# Shield.net
KiCad netlist of a schematic drawn in Altium Designer
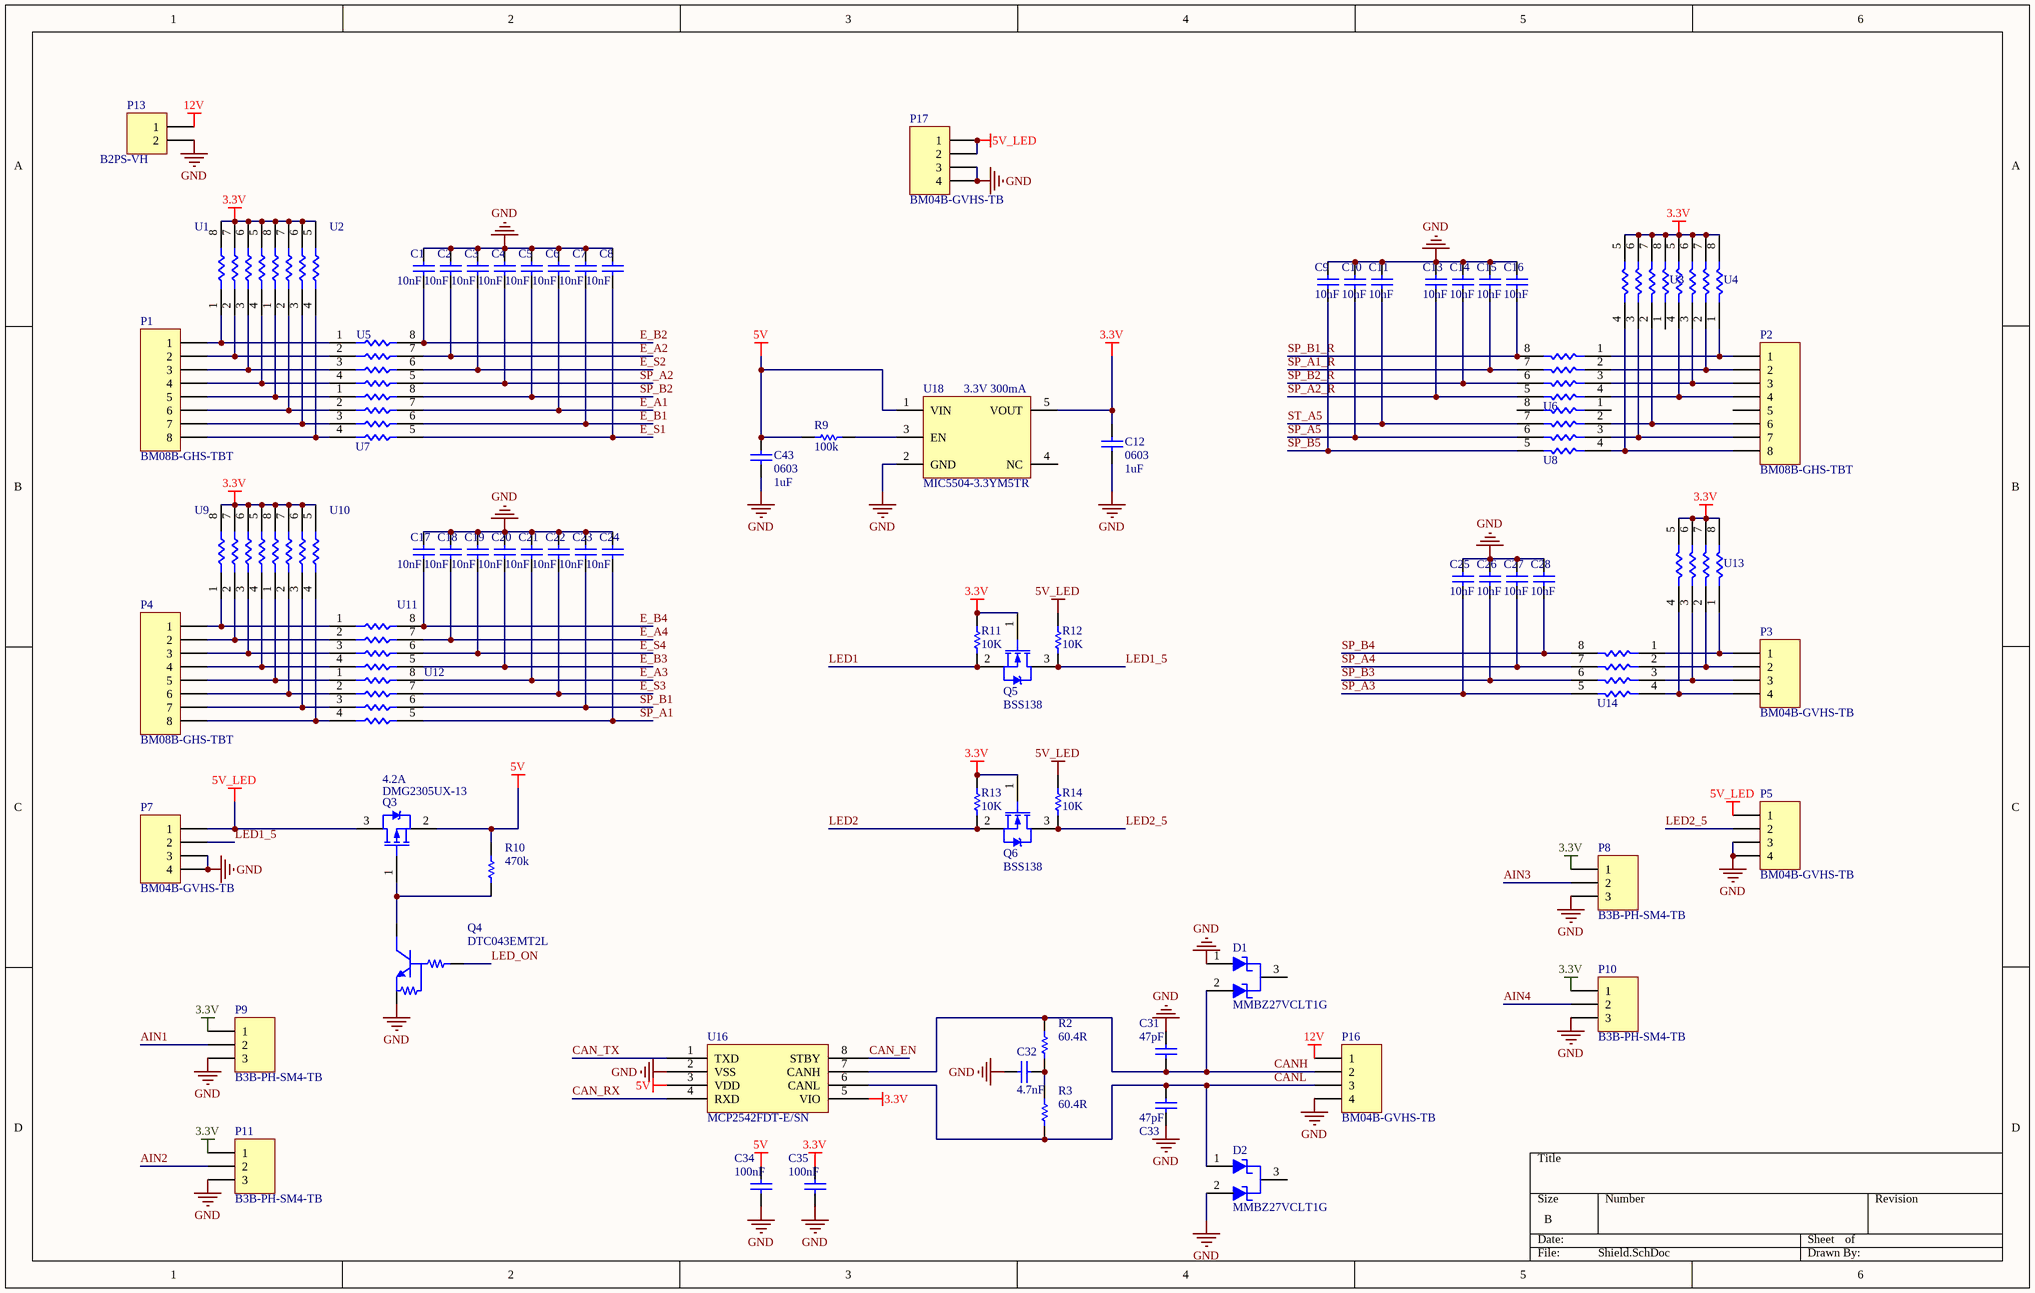
[diagram p0: Shield.SchDoc]

(export (version "E")
  (design (tool "Eeschema 10.0.6"))
  (components
    (comp (ref "C1")
      (value "10nF")
      (footprint "C0402")
      (description "Multilayer Ceramic Capacitor, 0.01 uF, 16 V, ± 5%, C0G (NP0), 0402 [1005 Metric]")
      (fields
        (field (name "MANUFACTURER") "Yageo")
        (field (name "MANUFACTURER PART NUMBER") "CC0402KRX7R7BB103")
      )
      (libsource (lib "Miscellaneous Devices") (part "Cap"))
    )
    (comp (ref "C2")
      (value "10nF")
      (footprint "C0402")
      (description "Multilayer Ceramic Capacitor, 0.01 uF, 16 V, ± 5%, C0G (NP0), 0402 [1005 Metric]")
      (fields
        (field (name "MANUFACTURER") "Yageo")
        (field (name "MANUFACTURER PART NUMBER") "CC0402KRX7R7BB103")
      )
      (libsource (lib "Miscellaneous Devices") (part "Cap"))
    )
    (comp (ref "C3")
      (value "10nF")
      (footprint "C0402")
      (description "Multilayer Ceramic Capacitor, 0.01 uF, 16 V, ± 5%, C0G (NP0), 0402 [1005 Metric]")
      (fields
        (field (name "MANUFACTURER") "Yageo")
        (field (name "MANUFACTURER PART NUMBER") "CC0402KRX7R7BB103")
      )
      (libsource (lib "Miscellaneous Devices") (part "Cap"))
    )
    (comp (ref "C4")
      (value "10nF")
      (footprint "C0402")
      (description "Multilayer Ceramic Capacitor, 0.01 uF, 16 V, ± 5%, C0G (NP0), 0402 [1005 Metric]")
      (fields
        (field (name "MANUFACTURER") "Yageo")
        (field (name "MANUFACTURER PART NUMBER") "CC0402KRX7R7BB103")
      )
      (libsource (lib "Miscellaneous Devices") (part "Cap"))
    )
    (comp (ref "C5")
      (value "10nF")
      (footprint "C0402")
      (description "Multilayer Ceramic Capacitor, 0.01 uF, 16 V, ± 5%, C0G (NP0), 0402 [1005 Metric]")
      (fields
        (field (name "MANUFACTURER") "Yageo")
        (field (name "MANUFACTURER PART NUMBER") "CC0402KRX7R7BB103")
      )
      (libsource (lib "Miscellaneous Devices") (part "Cap"))
    )
    (comp (ref "C6")
      (value "10nF")
      (footprint "C0402")
      (description "Multilayer Ceramic Capacitor, 0.01 uF, 16 V, ± 5%, C0G (NP0), 0402 [1005 Metric]")
      (fields
        (field (name "MANUFACTURER") "Yageo")
        (field (name "MANUFACTURER PART NUMBER") "CC0402KRX7R7BB103")
      )
      (libsource (lib "Miscellaneous Devices") (part "Cap"))
    )
    (comp (ref "C7")
      (value "10nF")
      (footprint "C0402")
      (description "Multilayer Ceramic Capacitor, 0.01 uF, 16 V, ± 5%, C0G (NP0), 0402 [1005 Metric]")
      (fields
        (field (name "MANUFACTURER") "Yageo")
        (field (name "MANUFACTURER PART NUMBER") "CC0402KRX7R7BB103")
      )
      (libsource (lib "Miscellaneous Devices") (part "Cap"))
    )
    (comp (ref "C8")
      (value "10nF")
      (footprint "C0402")
      (description "Multilayer Ceramic Capacitor, 0.01 uF, 16 V, ± 5%, C0G (NP0), 0402 [1005 Metric]")
      (fields
        (field (name "MANUFACTURER") "Yageo")
        (field (name "MANUFACTURER PART NUMBER") "CC0402KRX7R7BB103")
      )
      (libsource (lib "Miscellaneous Devices") (part "Cap"))
    )
    (comp (ref "C9")
      (value "10nF")
      (footprint "C0402")
      (description "Multilayer Ceramic Capacitor, 0.01 uF, 16 V, ± 5%, C0G (NP0), 0402 [1005 Metric]")
      (fields
        (field (name "MANUFACTURER") "Yageo")
        (field (name "MANUFACTURER PART NUMBER") "CC0402KRX7R7BB103")
      )
      (libsource (lib "Miscellaneous Devices") (part "Cap"))
    )
    (comp (ref "C10")
      (value "10nF")
      (footprint "C0402")
      (description "Multilayer Ceramic Capacitor, 0.01 uF, 16 V, ± 5%, C0G (NP0), 0402 [1005 Metric]")
      (fields
        (field (name "MANUFACTURER") "Yageo")
        (field (name "MANUFACTURER PART NUMBER") "CC0402KRX7R7BB103")
      )
      (libsource (lib "Miscellaneous Devices") (part "Cap"))
    )
    (comp (ref "C11")
      (value "10nF")
      (footprint "C0402")
      (description "Multilayer Ceramic Capacitor, 0.01 uF, 16 V, ± 5%, C0G (NP0), 0402 [1005 Metric]")
      (fields
        (field (name "MANUFACTURER") "Yageo")
        (field (name "MANUFACTURER PART NUMBER") "CC0402KRX7R7BB103")
      )
      (libsource (lib "Miscellaneous Devices") (part "Cap"))
    )
    (comp (ref "C12")
      (value "0603")
      (footprint "C0603")
      (description "Capacitor")
      (fields (field (name "ALTIUM_VALUE") "1uF") (field (name "PUBLISHER") "Altium Limited"))
      (libsource (lib "Miscellaneous Devices") (part "Cap"))
    )
    (comp (ref "C13")
      (value "10nF")
      (footprint "C0402")
      (description "Multilayer Ceramic Capacitor, 0.01 uF, 16 V, ± 5%, C0G (NP0), 0402 [1005 Metric]")
      (fields
        (field (name "MANUFACTURER") "Yageo")
        (field (name "MANUFACTURER PART NUMBER") "CC0402KRX7R7BB103")
      )
      (libsource (lib "Miscellaneous Devices") (part "Cap"))
    )
    (comp (ref "C14")
      (value "10nF")
      (footprint "C0402")
      (description "Multilayer Ceramic Capacitor, 0.01 uF, 16 V, ± 5%, C0G (NP0), 0402 [1005 Metric]")
      (fields
        (field (name "MANUFACTURER") "Yageo")
        (field (name "MANUFACTURER PART NUMBER") "CC0402KRX7R7BB103")
      )
      (libsource (lib "Miscellaneous Devices") (part "Cap"))
    )
    (comp (ref "C15")
      (value "10nF")
      (footprint "C0402")
      (description "Multilayer Ceramic Capacitor, 0.01 uF, 16 V, ± 5%, C0G (NP0), 0402 [1005 Metric]")
      (fields
        (field (name "MANUFACTURER") "Yageo")
        (field (name "MANUFACTURER PART NUMBER") "CC0402KRX7R7BB103")
      )
      (libsource (lib "Miscellaneous Devices") (part "Cap"))
    )
    (comp (ref "C16")
      (value "10nF")
      (footprint "C0402")
      (description "Multilayer Ceramic Capacitor, 0.01 uF, 16 V, ± 5%, C0G (NP0), 0402 [1005 Metric]")
      (fields
        (field (name "MANUFACTURER") "Yageo")
        (field (name "MANUFACTURER PART NUMBER") "CC0402KRX7R7BB103")
      )
      (libsource (lib "Miscellaneous Devices") (part "Cap"))
    )
    (comp (ref "C17")
      (value "10nF")
      (footprint "C0402")
      (description "Multilayer Ceramic Capacitor, 0.01 uF, 16 V, ± 5%, C0G (NP0), 0402 [1005 Metric]")
      (fields
        (field (name "MANUFACTURER") "Yageo")
        (field (name "MANUFACTURER PART NUMBER") "CC0402KRX7R7BB103")
      )
      (libsource (lib "Miscellaneous Devices") (part "Cap"))
    )
    (comp (ref "C18")
      (value "10nF")
      (footprint "C0402")
      (description "Multilayer Ceramic Capacitor, 0.01 uF, 16 V, ± 5%, C0G (NP0), 0402 [1005 Metric]")
      (fields
        (field (name "MANUFACTURER") "Yageo")
        (field (name "MANUFACTURER PART NUMBER") "CC0402KRX7R7BB103")
      )
      (libsource (lib "Miscellaneous Devices") (part "Cap"))
    )
    (comp (ref "C19")
      (value "10nF")
      (footprint "C0402")
      (description "Multilayer Ceramic Capacitor, 0.01 uF, 16 V, ± 5%, C0G (NP0), 0402 [1005 Metric]")
      (fields
        (field (name "MANUFACTURER") "Yageo")
        (field (name "MANUFACTURER PART NUMBER") "CC0402KRX7R7BB103")
      )
      (libsource (lib "Miscellaneous Devices") (part "Cap"))
    )
    (comp (ref "C20")
      (value "10nF")
      (footprint "C0402")
      (description "Multilayer Ceramic Capacitor, 0.01 uF, 16 V, ± 5%, C0G (NP0), 0402 [1005 Metric]")
      (fields
        (field (name "MANUFACTURER") "Yageo")
        (field (name "MANUFACTURER PART NUMBER") "CC0402KRX7R7BB103")
      )
      (libsource (lib "Miscellaneous Devices") (part "Cap"))
    )
    (comp (ref "C21")
      (value "10nF")
      (footprint "C0402")
      (description "Multilayer Ceramic Capacitor, 0.01 uF, 16 V, ± 5%, C0G (NP0), 0402 [1005 Metric]")
      (fields
        (field (name "MANUFACTURER") "Yageo")
        (field (name "MANUFACTURER PART NUMBER") "CC0402KRX7R7BB103")
      )
      (libsource (lib "Miscellaneous Devices") (part "Cap"))
    )
    (comp (ref "C22")
      (value "10nF")
      (footprint "C0402")
      (description "Multilayer Ceramic Capacitor, 0.01 uF, 16 V, ± 5%, C0G (NP0), 0402 [1005 Metric]")
      (fields
        (field (name "MANUFACTURER") "Yageo")
        (field (name "MANUFACTURER PART NUMBER") "CC0402KRX7R7BB103")
      )
      (libsource (lib "Miscellaneous Devices") (part "Cap"))
    )
    (comp (ref "C23")
      (value "10nF")
      (footprint "C0402")
      (description "Multilayer Ceramic Capacitor, 0.01 uF, 16 V, ± 5%, C0G (NP0), 0402 [1005 Metric]")
      (fields
        (field (name "MANUFACTURER") "Yageo")
        (field (name "MANUFACTURER PART NUMBER") "CC0402KRX7R7BB103")
      )
      (libsource (lib "Miscellaneous Devices") (part "Cap"))
    )
    (comp (ref "C24")
      (value "10nF")
      (footprint "C0402")
      (description "Multilayer Ceramic Capacitor, 0.01 uF, 16 V, ± 5%, C0G (NP0), 0402 [1005 Metric]")
      (fields
        (field (name "MANUFACTURER") "Yageo")
        (field (name "MANUFACTURER PART NUMBER") "CC0402KRX7R7BB103")
      )
      (libsource (lib "Miscellaneous Devices") (part "Cap"))
    )
    (comp (ref "C25")
      (value "10nF")
      (footprint "C0402")
      (description "Multilayer Ceramic Capacitor, 0.01 uF, 16 V, ± 5%, C0G (NP0), 0402 [1005 Metric]")
      (fields
        (field (name "MANUFACTURER") "Yageo")
        (field (name "MANUFACTURER PART NUMBER") "CC0402KRX7R7BB103")
      )
      (libsource (lib "Miscellaneous Devices") (part "Cap"))
    )
    (comp (ref "C26")
      (value "10nF")
      (footprint "C0402")
      (description "Multilayer Ceramic Capacitor, 0.01 uF, 16 V, ± 5%, C0G (NP0), 0402 [1005 Metric]")
      (fields
        (field (name "MANUFACTURER") "Yageo")
        (field (name "MANUFACTURER PART NUMBER") "CC0402KRX7R7BB103")
      )
      (libsource (lib "Miscellaneous Devices") (part "Cap"))
    )
    (comp (ref "C27")
      (value "10nF")
      (footprint "C0402")
      (description "Multilayer Ceramic Capacitor, 0.01 uF, 16 V, ± 5%, C0G (NP0), 0402 [1005 Metric]")
      (fields
        (field (name "MANUFACTURER") "Yageo")
        (field (name "MANUFACTURER PART NUMBER") "CC0402KRX7R7BB103")
      )
      (libsource (lib "Miscellaneous Devices") (part "Cap"))
    )
    (comp (ref "C28")
      (value "10nF")
      (footprint "C0402")
      (description "Multilayer Ceramic Capacitor, 0.01 uF, 16 V, ± 5%, C0G (NP0), 0402 [1005 Metric]")
      (fields
        (field (name "MANUFACTURER") "Yageo")
        (field (name "MANUFACTURER PART NUMBER") "CC0402KRX7R7BB103")
      )
      (libsource (lib "Miscellaneous Devices") (part "Cap"))
    )
    (comp (ref "C31")
      (value "47pF")
      (footprint "C0402")
      (description "Cap Cer 47PF 100V C0G/NP0 0402")
      (fields
        (field (name "MANUFACTURER") "Wurth Electronics")
        (field (name "MANUFACTURER PART NUMBER") "885012005078")
      )
      (libsource (lib "Miscellaneous Devices") (part "Cap"))
    )
    (comp (ref "C32")
      (value "4.7nF")
      (footprint "C0402")
      (description "Cap Cer 4700PF 100V X7R 0402")
      (fields
        (field (name "MANUFACTURER") "Wurth Electronics")
        (field (name "MANUFACTURER PART NUMBER") "885012205084")
      )
      (libsource (lib "Miscellaneous Devices") (part "Cap"))
    )
    (comp (ref "C33")
      (value "47pF")
      (footprint "C0402")
      (description "Cap Cer 47PF 100V C0G/NP0 0402")
      (fields
        (field (name "MANUFACTURER") "Wurth Electronics")
        (field (name "MANUFACTURER PART NUMBER") "885012005078")
      )
      (libsource (lib "Miscellaneous Devices") (part "Cap"))
    )
    (comp (ref "C34")
      (value "100nF")
      (footprint "C0402")
      (description "100nF ±10% 16V X7R 0402 Multilayer Ceramic Capacitors MLCC - SMD/SMT RoHS")
      (fields
        (field (name "MANUFACTURER") "KEMET")
        (field (name "MANUFACTURER PART NUMBER") "C0402C104K4RAC-TU")
      )
      (libsource (lib "Miscellaneous Devices") (part "Cap"))
    )
    (comp (ref "C35")
      (value "100nF")
      (footprint "C0402")
      (description "100nF ±10% 16V X7R 0402 Multilayer Ceramic Capacitors MLCC - SMD/SMT RoHS")
      (fields
        (field (name "MANUFACTURER") "KEMET")
        (field (name "MANUFACTURER PART NUMBER") "C0402C104K4RAC-TU")
      )
      (libsource (lib "Miscellaneous Devices") (part "Cap"))
    )
    (comp (ref "C43")
      (value "0603")
      (footprint "C0603")
      (description "Capacitor")
      (fields (field (name "ALTIUM_VALUE") "1uF") (field (name "PUBLISHER") "Altium Limited"))
      (libsource (lib "Miscellaneous Devices") (part "Cap"))
    )
    (comp (ref "D1")
      (value "MMBZ27VCLT1G")
      (footprint "SOT-23")
      (description "TVS DIODE 22VWM 38VC SOT23")
      (fields (field (name "MANUFACTURER") "ON Semiconductor"))
      (libsource (lib "Schlib1") (part "MMBZ27VCLT1G"))
    )
    (comp (ref "D2")
      (value "MMBZ27VCLT1G")
      (footprint "SOT-23")
      (description "TVS DIODE 22VWM 38VC SOT23")
      (fields (field (name "MANUFACTURER") "ON Semiconductor"))
      (libsource (lib "Schlib1") (part "MMBZ27VCLT1G"))
    )
    (comp (ref "P1")
      (value "BM08B-GHS-TBT")
      (footprint "CONN-BM08B-GHS-TBT")
      (description "Header, 8-Pin")
      (fields (field (name "MANUFACTURER") "JST"))
      (libsource (lib "Miscellaneous Connectors") (part "Header 8"))
    )
    (comp (ref "P2")
      (value "BM08B-GHS-TBT")
      (footprint "CONN-BM08B-GHS-TBT - INVERTED")
      (description "Header, 8-Pin")
      (fields (field (name "MANUFACTURER") "JST"))
      (libsource (lib "") (part "Header 8_1"))
    )
    (comp (ref "P3")
      (value "BM04B-GVHS-TB")
      (footprint "CONN-SM04B-GHSV-TB - INVERTED")
      (description "Conn Header SMD 4POS 1.25MM")
      (fields (field (name "MANUFACTURER") "JST"))
      (libsource (lib "") (part "Header 4_1"))
    )
    (comp (ref "P4")
      (value "BM08B-GHS-TBT")
      (footprint "CONN-BM08B-GHS-TBT")
      (description "Header, 8-Pin")
      (fields (field (name "MANUFACTURER") "JST"))
      (libsource (lib "Miscellaneous Connectors") (part "Header 8"))
    )
    (comp (ref "P5")
      (value "BM04B-GVHS-TB")
      (footprint "CONN-SM04B-GHSV-TB - INVERTED")
      (description "Conn Header SMD 4POS 1.25MM")
      (fields (field (name "MANUFACTURER") "JST"))
      (libsource (lib "") (part "Header 4_1"))
    )
    (comp (ref "P7")
      (value "BM04B-GVHS-TB")
      (footprint "CONN-SM04B-GHSV-TB")
      (description "Conn Header SMD 4POS 1.25MM")
      (fields (field (name "MANUFACTURER") "JST"))
      (libsource (lib "Miscellaneous Connectors") (part "Header 4"))
    )
    (comp (ref "P8")
      (value "B3B-PH-SM4-TB")
      (footprint "CONN-B3B-PH-SM4-TB")
      (description "Header B3B-PH-SM4-TB, 2.00mm, 3-contacts, top entry, SMT /1000/reel")
      (fields (field (name "MANUFACTURER") "JST"))
      (libsource (lib "Miscellaneous Connectors") (part "Header 3"))
    )
    (comp (ref "P9")
      (value "B3B-PH-SM4-TB")
      (footprint "CONN-B3B-PH-SM4-TB")
      (description "Header B3B-PH-SM4-TB, 2.00mm, 3-contacts, top entry, SMT /1000/reel")
      (fields (field (name "MANUFACTURER") "JST"))
      (libsource (lib "Miscellaneous Connectors") (part "Header 3"))
    )
    (comp (ref "P10")
      (value "B3B-PH-SM4-TB")
      (footprint "CONN-B3B-PH-SM4-TB")
      (description "Header B3B-PH-SM4-TB, 2.00mm, 3-contacts, top entry, SMT /1000/reel")
      (fields (field (name "MANUFACTURER") "JST"))
      (libsource (lib "Miscellaneous Connectors") (part "Header 3"))
    )
    (comp (ref "P11")
      (value "B3B-PH-SM4-TB")
      (footprint "CONN-B3B-PH-SM4-TB")
      (description "Header B3B-PH-SM4-TB, 2.00mm, 3-contacts, top entry, SMT /1000/reel")
      (fields (field (name "MANUFACTURER") "JST"))
      (libsource (lib "Miscellaneous Connectors") (part "Header 3"))
    )
    (comp (ref "P13")
      (value "B2PS-VH")
      (footprint "CONN-B2PS-VH")
      (description "Header B2PS-VH, 3.96mm, 2-contacts, side entry, THT/1000/box")
      (fields (field (name "MANUFACTURER") "JST"))
      (libsource (lib "Miscellaneous Connectors") (part "Header 2"))
    )
    (comp (ref "P16")
      (value "BM04B-GVHS-TB")
      (footprint "CONN-SM04B-GHSV-TB - INVERTED")
      (description "Conn Header SMD 4POS 1.25MM")
      (fields (field (name "MANUFACTURER") "JST"))
      (libsource (lib "") (part "Header 4_1"))
    )
    (comp (ref "P17")
      (value "BM04B-GVHS-TB")
      (footprint "CONN-SM04B-GHSV-TB - INVERTED")
      (description "Conn Header SMD 4POS 1.25MM")
      (fields (field (name "MANUFACTURER") "JST"))
      (libsource (lib "Miscellaneous Connectors") (part "Header 4"))
    )
    (comp (ref "Q3")
      (value "DMG2305UX-13")
      (footprint "SOT23-3")
      (description "MOSFET P-CH 20V 4.2A SOT23")
      (fields (field (name "MANUFACTURER") "Diodes") (field (name "CONTINUOUS DRAIN CURRENT (ID)") "4.2A"))
      (libsource (lib "Symbols") (part "ZXMP10A13FTA"))
    )
    (comp (ref "Q4")
      (value "DTC043EMT2L")
      (footprint "SOT-723")
      (description "TRANS PREBIAS NPN 50V VMT3")
      (fields (field (name "MANUFACTURER") "Rohm"))
      (libsource (lib "Schlib1") (part "DTC043EMT2L"))
    )
    (comp (ref "Q5")
      (value "BSS138")
      (footprint "SOT-23")
      (description "N-Channel Power MOSFET")
      (libsource (lib "Miscellaneous Devices") (part "NMOS-2"))
    )
    (comp (ref "Q6")
      (value "BSS138")
      (footprint "SOT-23")
      (description "N-Channel Power MOSFET")
      (libsource (lib "Miscellaneous Devices") (part "NMOS-2"))
    )
    (comp (ref "R2")
      (value "60.4R")
      (footprint "R0402")
      (description "Res Thick Film 0402 60.4 Ohm 1% 1/16W ±100ppm/°C Molded SMD SMD Paper T/R")
      (fields
        (field (name "MANUFACTURER") "Vishay")
        (field (name "MANUFACTURER PART NUMBER") "CRCW040260R4FKED")
      )
      (libsource (lib "Miscellaneous Devices") (part "Res1"))
    )
    (comp (ref "R3")
      (value "60.4R")
      (footprint "R0402")
      (description "Res Thick Film 0402 60.4 Ohm 1% 1/16W ±100ppm/°C Molded SMD SMD Paper T/R")
      (fields
        (field (name "MANUFACTURER") "Vishay")
        (field (name "MANUFACTURER PART NUMBER") "CRCW040260R4FKED")
      )
      (libsource (lib "Miscellaneous Devices") (part "Res1"))
    )
    (comp (ref "R9")
      (value "100k")
      (footprint "R0402")
      (description "Res Thick Film 0402 60.4 Ohm 1% 1/16W ±100ppm/°C Molded SMD SMD Paper T/R")
      (libsource (lib "Miscellaneous Devices") (part "Res1"))
    )
    (comp (ref "R10")
      (value "470k")
      (footprint "R0402")
      (description "Res Thick Film 0402 60.4 Ohm 1% 1/16W ±100ppm/°C Molded SMD SMD Paper T/R")
      (libsource (lib "Miscellaneous Devices") (part "Res1"))
    )
    (comp (ref "R11")
      (value "10K")
      (footprint "R0402")
      (description "RES SMD 10 KOHM 1% 1/16W 0402")
      (fields (field (name "Comment") "Res1"))
      (libsource (lib "Miscellaneous Devices") (part "Res1"))
    )
    (comp (ref "R12")
      (value "10K")
      (footprint "R0402")
      (description "RES SMD 10 KOHM 1% 1/16W 0402")
      (fields (field (name "Comment") "Res1"))
      (libsource (lib "Miscellaneous Devices") (part "Res1"))
    )
    (comp (ref "R13")
      (value "10K")
      (footprint "R0402")
      (description "RES SMD 10 KOHM 1% 1/16W 0402")
      (fields (field (name "Comment") "Res1"))
      (libsource (lib "Miscellaneous Devices") (part "Res1"))
    )
    (comp (ref "R14")
      (value "10K")
      (footprint "R0402")
      (description "RES SMD 10 KOHM 1% 1/16W 0402")
      (fields (field (name "Comment") "Res1"))
      (libsource (lib "Miscellaneous Devices") (part "Res1"))
    )
    (comp (ref "U1")
      (value "CAY16-1002F4LF")
      (footprint "RES_ARRAY_4")
      (description "Res Thick Film Array 10K Ohm 1% 0.25W(1/4W) ±200ppm/C ISOL 8-Pin 1206(4 X 0603) Convex SMD T/R")
      (fields (field (name "MANUFACTURER") "Bourns") (field (name "TOLERANCE") "1%"))
      (libsource (lib "Schlib1") (part "ResArray4"))
    )
    (comp (ref "U2")
      (value "CAY16-1002F4LF")
      (footprint "RES_ARRAY_4")
      (description "Res Thick Film Array 10K Ohm 1% 0.25W(1/4W) ±200ppm/C ISOL 8-Pin 1206(4 X 0603) Convex SMD T/R")
      (fields (field (name "MANUFACTURER") "Bourns") (field (name "TOLERANCE") "1%"))
      (libsource (lib "Schlib1") (part "ResArray4"))
    )
    (comp (ref "U3")
      (value "CAY16-1002F4LF")
      (footprint "RES_ARRAY_4 - INVERTED")
      (description "Res Thick Film Array 10K Ohm 1% 0.25W(1/4W) ±200ppm/C ISOL 8-Pin 1206(4 X 0603) Convex SMD T/R")
      (fields (field (name "MANUFACTURER") "Bourns") (field (name "TOLERANCE") "1%"))
      (libsource (lib "Schlib1") (part "ResArray4"))
    )
    (comp (ref "U4")
      (value "CAY16-1002F4LF")
      (footprint "RES_ARRAY_4 - INVERTED")
      (description "Res Thick Film Array 10K Ohm 1% 0.25W(1/4W) ±200ppm/C ISOL 8-Pin 1206(4 X 0603) Convex SMD T/R")
      (fields (field (name "MANUFACTURER") "Bourns") (field (name "TOLERANCE") "1%"))
      (libsource (lib "Schlib1") (part "ResArray4"))
    )
    (comp (ref "U5")
      (value "CAY16-1002F4LF")
      (footprint "RES_ARRAY_4 - INVERTED")
      (description "Res Thick Film Array 10K Ohm 1% 0.25W(1/4W) ±200ppm/C ISOL 8-Pin 1206(4 X 0603) Convex SMD T/R")
      (fields (field (name "MANUFACTURER") "Bourns") (field (name "TOLERANCE") "1%"))
      (libsource (lib "Schlib1") (part "ResArray4"))
    )
    (comp (ref "U6")
      (value "CAY16-1002F4LF")
      (footprint "RES_ARRAY_4")
      (description "Res Thick Film Array 10K Ohm 1% 0.25W(1/4W) ±200ppm/C ISOL 8-Pin 1206(4 X 0603) Convex SMD T/R")
      (fields (field (name "MANUFACTURER") "Bourns") (field (name "TOLERANCE") "1%"))
      (libsource (lib "Schlib1") (part "ResArray4"))
    )
    (comp (ref "U7")
      (value "CAY16-1002F4LF")
      (footprint "RES_ARRAY_4 - INVERTED")
      (description "Res Thick Film Array 10K Ohm 1% 0.25W(1/4W) ±200ppm/C ISOL 8-Pin 1206(4 X 0603) Convex SMD T/R")
      (fields (field (name "MANUFACTURER") "Bourns") (field (name "TOLERANCE") "1%"))
      (libsource (lib "Schlib1") (part "ResArray4"))
    )
    (comp (ref "U8")
      (value "CAY16-1002F4LF")
      (footprint "RES_ARRAY_4")
      (description "Res Thick Film Array 10K Ohm 1% 0.25W(1/4W) ±200ppm/C ISOL 8-Pin 1206(4 X 0603) Convex SMD T/R")
      (fields (field (name "MANUFACTURER") "Bourns") (field (name "TOLERANCE") "1%"))
      (libsource (lib "Schlib1") (part "ResArray4"))
    )
    (comp (ref "U9")
      (value "CAY16-1002F4LF")
      (footprint "RES_ARRAY_4")
      (description "Res Thick Film Array 10K Ohm 1% 0.25W(1/4W) ±200ppm/C ISOL 8-Pin 1206(4 X 0603) Convex SMD T/R")
      (fields (field (name "MANUFACTURER") "Bourns") (field (name "TOLERANCE") "1%"))
      (libsource (lib "Schlib1") (part "ResArray4"))
    )
    (comp (ref "U10")
      (value "CAY16-1002F4LF")
      (footprint "RES_ARRAY_4")
      (description "Res Thick Film Array 10K Ohm 1% 0.25W(1/4W) ±200ppm/C ISOL 8-Pin 1206(4 X 0603) Convex SMD T/R")
      (fields (field (name "MANUFACTURER") "Bourns") (field (name "TOLERANCE") "1%"))
      (libsource (lib "Schlib1") (part "ResArray4"))
    )
    (comp (ref "U11")
      (value "CAY16-1002F4LF")
      (footprint "RES_ARRAY_4 - INVERTED")
      (description "Res Thick Film Array 10K Ohm 1% 0.25W(1/4W) ±200ppm/C ISOL 8-Pin 1206(4 X 0603) Convex SMD T/R")
      (fields (field (name "MANUFACTURER") "Bourns") (field (name "TOLERANCE") "1%"))
      (libsource (lib "Schlib1") (part "ResArray4"))
    )
    (comp (ref "U12")
      (value "CAY16-1002F4LF")
      (footprint "RES_ARRAY_4 - INVERTED")
      (description "Res Thick Film Array 10K Ohm 1% 0.25W(1/4W) ±200ppm/C ISOL 8-Pin 1206(4 X 0603) Convex SMD T/R")
      (fields (field (name "MANUFACTURER") "Bourns") (field (name "TOLERANCE") "1%"))
      (libsource (lib "Schlib1") (part "ResArray4"))
    )
    (comp (ref "U13")
      (value "CAY16-1002F4LF")
      (footprint "RES_ARRAY_4")
      (description "Res Thick Film Array 10K Ohm 1% 0.25W(1/4W) ±200ppm/C ISOL 8-Pin 1206(4 X 0603) Convex SMD T/R")
      (fields (field (name "MANUFACTURER") "Bourns") (field (name "TOLERANCE") "1%"))
      (libsource (lib "Schlib1") (part "ResArray4"))
    )
    (comp (ref "U14")
      (value "CAY16-1002F4LF")
      (footprint "RES_ARRAY_4")
      (description "Res Thick Film Array 10K Ohm 1% 0.25W(1/4W) ±200ppm/C ISOL 8-Pin 1206(4 X 0603) Convex SMD T/R")
      (fields (field (name "MANUFACTURER") "Bourns") (field (name "TOLERANCE") "1%"))
      (libsource (lib "Schlib1") (part "ResArray4"))
    )
    (comp (ref "U16")
      (value "MCP2542FDT-E/SN")
      (footprint "SOIC-8(150MIL)")
      (description "Can Interface IC Can Fd Transceiver - 8SOIC T/r")
      (fields (field (name "MANUFACTURER") "Microchip"))
      (libsource (lib "Schlib1") (part "MCP2542FDT-E/SN"))
    )
    (comp (ref "U18")
      (value "MIC5504-3.3YM5TR")
      (footprint "SOT23-5")
      (description "IC REG LINEAR 3.3V 300MA SOT23-5")
      (fields (field (name "MANUFACTURER") "Microchip Micrel") (field (name "ALTIUM_VALUE") "3.3V 300mA"))
      (libsource (lib "Footprints") (part "MIC5504-3.3YM5TR"))
    )
  )
  (nets
    (net (code "1") (name "/AIN1") (class "Default")
      (node (ref "P9") (pin "2") (pinfunction "2_2") (pintype "passive"))
    )
    (net (code "2") (name "/AIN2") (class "Default")
      (node (ref "P11") (pin "2") (pinfunction "2_2") (pintype "passive"))
    )
    (net (code "3") (name "/AIN3") (class "Default")
      (node (ref "P8") (pin "2") (pinfunction "2_2") (pintype "passive"))
    )
    (net (code "4") (name "/AIN4") (class "Default")
      (node (ref "P10") (pin "2") (pinfunction "2_2") (pintype "passive"))
    )
    (net (code "5") (name "/CANH") (class "Default")
      (node (ref "C31") (pin "1") (pinfunction "1_1") (pintype "passive"))
      (node (ref "D1") (pin "2") (pinfunction "C_2") (pintype "passive"))
      (node (ref "P16") (pin "2") (pinfunction "2_2") (pintype "passive"))
      (node (ref "R2") (pin "2") (pinfunction "2_2") (pintype "passive"))
      (node (ref "U16") (pin "7") (pinfunction "CANH_7") (pintype "passive"))
    )
    (net (code "6") (name "/CANL") (class "Default")
      (node (ref "C33") (pin "2") (pinfunction "2_2") (pintype "passive"))
      (node (ref "D2") (pin "1") (pinfunction "1_1") (pintype "passive"))
      (node (ref "P16") (pin "3") (pinfunction "3_3") (pintype "passive"))
      (node (ref "R3") (pin "1") (pinfunction "1_1") (pintype "passive"))
      (node (ref "U16") (pin "6") (pinfunction "CANL_6") (pintype "passive"))
    )
    (net (code "7") (name "/CAN_EN") (class "Default")
      (node (ref "U16") (pin "8") (pinfunction "STBY_8") (pintype "passive"))
    )
    (net (code "8") (name "/CAN_RX") (class "Default")
      (node (ref "U16") (pin "4") (pinfunction "RXD_4") (pintype "passive"))
    )
    (net (code "9") (name "/CAN_TX") (class "Default")
      (node (ref "U16") (pin "1") (pinfunction "TXD_1") (pintype "passive"))
    )
    (net (code "10") (name "/E_A1") (class "Default")
      (node (ref "C6") (pin "1") (pinfunction "1_1") (pintype "passive"))
      (node (ref "U7") (pin "7") (pinfunction "7_7") (pintype "passive"))
    )
    (net (code "11") (name "/E_A2") (class "Default")
      (node (ref "C2") (pin "1") (pinfunction "1_1") (pintype "passive"))
      (node (ref "U5") (pin "7") (pinfunction "7_7") (pintype "passive"))
    )
    (net (code "12") (name "/E_A3") (class "Default")
      (node (ref "C21") (pin "1") (pinfunction "1_1") (pintype "passive"))
      (node (ref "U12") (pin "8") (pinfunction "8_8") (pintype "passive"))
    )
    (net (code "13") (name "/E_A4") (class "Default")
      (node (ref "C18") (pin "1") (pinfunction "1_1") (pintype "passive"))
      (node (ref "U11") (pin "7") (pinfunction "7_7") (pintype "passive"))
    )
    (net (code "14") (name "/E_B1") (class "Default")
      (node (ref "C7") (pin "1") (pinfunction "1_1") (pintype "passive"))
      (node (ref "U7") (pin "6") (pinfunction "6_6") (pintype "passive"))
    )
    (net (code "15") (name "/E_B2") (class "Default")
      (node (ref "C1") (pin "1") (pinfunction "1_1") (pintype "passive"))
      (node (ref "U5") (pin "8") (pinfunction "8_8") (pintype "passive"))
    )
    (net (code "16") (name "/E_B3") (class "Default")
      (node (ref "C20") (pin "1") (pinfunction "1_1") (pintype "passive"))
      (node (ref "U11") (pin "5") (pinfunction "5_5") (pintype "passive"))
    )
    (net (code "17") (name "/E_B4") (class "Default")
      (node (ref "C17") (pin "1") (pinfunction "1_1") (pintype "passive"))
      (node (ref "U11") (pin "8") (pinfunction "8_8") (pintype "passive"))
    )
    (net (code "18") (name "/E_S1") (class "Default")
      (node (ref "C8") (pin "1") (pinfunction "1_1") (pintype "passive"))
      (node (ref "U7") (pin "5") (pinfunction "5_5") (pintype "passive"))
    )
    (net (code "19") (name "/E_S2") (class "Default")
      (node (ref "C3") (pin "1") (pinfunction "1_1") (pintype "passive"))
      (node (ref "U5") (pin "6") (pinfunction "6_6") (pintype "passive"))
    )
    (net (code "20") (name "/E_S3") (class "Default")
      (node (ref "C22") (pin "1") (pinfunction "1_1") (pintype "passive"))
      (node (ref "U12") (pin "7") (pinfunction "7_7") (pintype "passive"))
    )
    (net (code "21") (name "/E_S4") (class "Default")
      (node (ref "C19") (pin "1") (pinfunction "1_1") (pintype "passive"))
      (node (ref "U11") (pin "6") (pinfunction "6_6") (pintype "passive"))
    )
    (net (code "22") (name "/LED1") (class "Default")
      (node (ref "Q5") (pin "2") (pinfunction "S_2") (pintype "passive"))
      (node (ref "R11") (pin "2") (pinfunction "2_2") (pintype "passive"))
    )
    (net (code "23") (name "/LED1_5") (class "Default")
      (node (ref "P7") (pin "2") (pinfunction "2_2") (pintype "passive"))
      (node (ref "Q5") (pin "3") (pinfunction "D_3") (pintype "passive"))
      (node (ref "R12") (pin "2") (pinfunction "2_2") (pintype "passive"))
    )
    (net (code "24") (name "/LED2") (class "Default")
      (node (ref "Q6") (pin "2") (pinfunction "S_2") (pintype "passive"))
      (node (ref "R13") (pin "2") (pinfunction "2_2") (pintype "passive"))
    )
    (net (code "25") (name "/LED2_5") (class "Default")
      (node (ref "P5") (pin "2") (pinfunction "2_2") (pintype "passive"))
      (node (ref "Q6") (pin "3") (pinfunction "D_3") (pintype "passive"))
      (node (ref "R14") (pin "2") (pinfunction "2_2") (pintype "passive"))
    )
    (net (code "26") (name "/LED_ON") (class "Default")
      (node (ref "Q4") (pin "1") (pinfunction "B_1") (pintype "passive"))
    )
    (net (code "27") (name "/SP_A1") (class "Default")
      (node (ref "C24") (pin "1") (pinfunction "1_1") (pintype "passive"))
      (node (ref "U12") (pin "5") (pinfunction "5_5") (pintype "passive"))
    )
    (net (code "28") (name "/SP_A1_R") (class "Default")
      (node (ref "C15") (pin "1") (pinfunction "1_1") (pintype "passive"))
      (node (ref "U6") (pin "7") (pinfunction "7_7") (pintype "passive"))
    )
    (net (code "29") (name "/SP_A2") (class "Default")
      (node (ref "C4") (pin "1") (pinfunction "1_1") (pintype "passive"))
      (node (ref "U5") (pin "5") (pinfunction "5_5") (pintype "passive"))
    )
    (net (code "30") (name "/SP_A2_R") (class "Default")
      (node (ref "C13") (pin "1") (pinfunction "1_1") (pintype "passive"))
      (node (ref "U6") (pin "5") (pinfunction "5_5") (pintype "passive"))
    )
    (net (code "31") (name "/SP_A3") (class "Default")
      (node (ref "C25") (pin "1") (pinfunction "1_1") (pintype "passive"))
      (node (ref "U14") (pin "5") (pinfunction "5_5") (pintype "passive"))
    )
    (net (code "32") (name "/SP_A4") (class "Default")
      (node (ref "C27") (pin "1") (pinfunction "1_1") (pintype "passive"))
      (node (ref "U14") (pin "7") (pinfunction "7_7") (pintype "passive"))
    )
    (net (code "33") (name "/SP_A5") (class "Default")
      (node (ref "C10") (pin "1") (pinfunction "1_1") (pintype "passive"))
      (node (ref "U8") (pin "6") (pinfunction "6_6") (pintype "passive"))
    )
    (net (code "34") (name "/SP_B1") (class "Default")
      (node (ref "C23") (pin "1") (pinfunction "1_1") (pintype "passive"))
      (node (ref "U12") (pin "6") (pinfunction "6_6") (pintype "passive"))
    )
    (net (code "35") (name "/SP_B1_R") (class "Default")
      (node (ref "C16") (pin "1") (pinfunction "1_1") (pintype "passive"))
      (node (ref "U6") (pin "8") (pinfunction "8_8") (pintype "passive"))
    )
    (net (code "36") (name "/SP_B2") (class "Default")
      (node (ref "C5") (pin "1") (pinfunction "1_1") (pintype "passive"))
      (node (ref "U7") (pin "8") (pinfunction "8_8") (pintype "passive"))
    )
    (net (code "37") (name "/SP_B2_R") (class "Default")
      (node (ref "C14") (pin "1") (pinfunction "1_1") (pintype "passive"))
      (node (ref "U6") (pin "6") (pinfunction "6_6") (pintype "passive"))
    )
    (net (code "38") (name "/SP_B3") (class "Default")
      (node (ref "C26") (pin "1") (pinfunction "1_1") (pintype "passive"))
      (node (ref "U14") (pin "6") (pinfunction "6_6") (pintype "passive"))
    )
    (net (code "39") (name "/SP_B4") (class "Default")
      (node (ref "C28") (pin "1") (pinfunction "1_1") (pintype "passive"))
      (node (ref "U14") (pin "8") (pinfunction "8_8") (pintype "passive"))
    )
    (net (code "40") (name "/SP_B5") (class "Default")
      (node (ref "C9") (pin "1") (pinfunction "1_1") (pintype "passive"))
      (node (ref "U8") (pin "5") (pinfunction "5_5") (pintype "passive"))
    )
    (net (code "41") (name "/ST_A5") (class "Default")
      (node (ref "C11") (pin "1") (pinfunction "1_1") (pintype "passive"))
      (node (ref "U8") (pin "7") (pinfunction "7_7") (pintype "passive"))
    )
    (net (code "42") (name "3.3V") (class "Default")
      (node (ref "C12") (pin "2") (pinfunction "2_2") (pintype "passive"))
      (node (ref "C35") (pin "2") (pinfunction "2_2") (pintype "passive"))
      (node (ref "P10") (pin "1") (pinfunction "1_1") (pintype "passive"))
      (node (ref "P11") (pin "1") (pinfunction "1_1") (pintype "passive"))
      (node (ref "P8") (pin "1") (pinfunction "1_1") (pintype "passive"))
      (node (ref "P9") (pin "1") (pinfunction "1_1") (pintype "passive"))
      (node (ref "Q5") (pin "1") (pinfunction "G_1") (pintype "passive"))
      (node (ref "Q6") (pin "1") (pinfunction "G_1") (pintype "passive"))
      (node (ref "R11") (pin "1") (pinfunction "1_1") (pintype "passive"))
      (node (ref "R13") (pin "1") (pinfunction "1_1") (pintype "passive"))
      (node (ref "U1") (pin "5") (pinfunction "5_5") (pintype "passive"))
      (node (ref "U1") (pin "6") (pinfunction "6_6") (pintype "passive"))
      (node (ref "U1") (pin "7") (pinfunction "7_7") (pintype "passive"))
      (node (ref "U1") (pin "8") (pinfunction "8_8") (pintype "passive"))
      (node (ref "U10") (pin "5") (pinfunction "5_5") (pintype "passive"))
      (node (ref "U10") (pin "6") (pinfunction "6_6") (pintype "passive"))
      (node (ref "U10") (pin "7") (pinfunction "7_7") (pintype "passive"))
      (node (ref "U10") (pin "8") (pinfunction "8_8") (pintype "passive"))
      (node (ref "U13") (pin "5") (pinfunction "5_5") (pintype "passive"))
      (node (ref "U13") (pin "6") (pinfunction "6_6") (pintype "passive"))
      (node (ref "U13") (pin "7") (pinfunction "7_7") (pintype "passive"))
      (node (ref "U13") (pin "8") (pinfunction "8_8") (pintype "passive"))
      (node (ref "U16") (pin "5") (pinfunction "VIO_5") (pintype "passive"))
      (node (ref "U18") (pin "5") (pinfunction "VOUT_5") (pintype "passive"))
      (node (ref "U2") (pin "5") (pinfunction "5_5") (pintype "passive"))
      (node (ref "U2") (pin "6") (pinfunction "6_6") (pintype "passive"))
      (node (ref "U2") (pin "7") (pinfunction "7_7") (pintype "passive"))
      (node (ref "U2") (pin "8") (pinfunction "8_8") (pintype "passive"))
      (node (ref "U3") (pin "5") (pinfunction "5_5") (pintype "passive"))
      (node (ref "U3") (pin "6") (pinfunction "6_6") (pintype "passive"))
      (node (ref "U3") (pin "7") (pinfunction "7_7") (pintype "passive"))
      (node (ref "U3") (pin "8") (pinfunction "8_8") (pintype "passive"))
      (node (ref "U4") (pin "5") (pinfunction "5_5") (pintype "passive"))
      (node (ref "U4") (pin "6") (pinfunction "6_6") (pintype "passive"))
      (node (ref "U4") (pin "7") (pinfunction "7_7") (pintype "passive"))
      (node (ref "U4") (pin "8") (pinfunction "8_8") (pintype "passive"))
      (node (ref "U9") (pin "5") (pinfunction "5_5") (pintype "passive"))
      (node (ref "U9") (pin "6") (pinfunction "6_6") (pintype "passive"))
      (node (ref "U9") (pin "7") (pinfunction "7_7") (pintype "passive"))
      (node (ref "U9") (pin "8") (pinfunction "8_8") (pintype "passive"))
    )
    (net (code "43") (name "5V") (class "Default")
      (node (ref "C34") (pin "2") (pinfunction "2_2") (pintype "passive"))
      (node (ref "C43") (pin "2") (pinfunction "2_2") (pintype "passive"))
      (node (ref "Q3") (pin "2") (pinfunction "S_2") (pintype "passive"))
      (node (ref "R10") (pin "2") (pinfunction "2_2") (pintype "passive"))
      (node (ref "R9") (pin "1") (pinfunction "1_1") (pintype "passive"))
      (node (ref "U16") (pin "3") (pinfunction "VDD_3") (pintype "passive"))
      (node (ref "U18") (pin "1") (pinfunction "VIN_1") (pintype "passive"))
    )
    (net (code "44") (name "5V_LED") (class "Default")
      (node (ref "P17") (pin "1") (pinfunction "1_1") (pintype "passive"))
      (node (ref "P17") (pin "2") (pinfunction "2_2") (pintype "passive"))
      (node (ref "P5") (pin "1") (pinfunction "1_1") (pintype "passive"))
      (node (ref "P7") (pin "1") (pinfunction "1_1") (pintype "passive"))
      (node (ref "Q3") (pin "3") (pinfunction "D_3") (pintype "passive"))
      (node (ref "R12") (pin "1") (pinfunction "1_1") (pintype "passive"))
      (node (ref "R14") (pin "1") (pinfunction "1_1") (pintype "passive"))
    )
    (net (code "45") (name "12V") (class "Default")
      (node (ref "P13") (pin "1") (pinfunction "1_1") (pintype "passive"))
      (node (ref "P16") (pin "1") (pinfunction "1_1") (pintype "passive"))
    )
    (net (code "46") (name "GND") (class "Default")
      (node (ref "C1") (pin "2") (pinfunction "2_2") (pintype "passive"))
      (node (ref "C10") (pin "2") (pinfunction "2_2") (pintype "passive"))
      (node (ref "C11") (pin "2") (pinfunction "2_2") (pintype "passive"))
      (node (ref "C12") (pin "1") (pinfunction "1_1") (pintype "passive"))
      (node (ref "C13") (pin "2") (pinfunction "2_2") (pintype "passive"))
      (node (ref "C14") (pin "2") (pinfunction "2_2") (pintype "passive"))
      (node (ref "C15") (pin "2") (pinfunction "2_2") (pintype "passive"))
      (node (ref "C16") (pin "2") (pinfunction "2_2") (pintype "passive"))
      (node (ref "C17") (pin "2") (pinfunction "2_2") (pintype "passive"))
      (node (ref "C18") (pin "2") (pinfunction "2_2") (pintype "passive"))
      (node (ref "C19") (pin "2") (pinfunction "2_2") (pintype "passive"))
      (node (ref "C2") (pin "2") (pinfunction "2_2") (pintype "passive"))
      (node (ref "C20") (pin "2") (pinfunction "2_2") (pintype "passive"))
      (node (ref "C21") (pin "2") (pinfunction "2_2") (pintype "passive"))
      (node (ref "C22") (pin "2") (pinfunction "2_2") (pintype "passive"))
      (node (ref "C23") (pin "2") (pinfunction "2_2") (pintype "passive"))
      (node (ref "C24") (pin "2") (pinfunction "2_2") (pintype "passive"))
      (node (ref "C25") (pin "2") (pinfunction "2_2") (pintype "passive"))
      (node (ref "C26") (pin "2") (pinfunction "2_2") (pintype "passive"))
      (node (ref "C27") (pin "2") (pinfunction "2_2") (pintype "passive"))
      (node (ref "C28") (pin "2") (pinfunction "2_2") (pintype "passive"))
      (node (ref "C3") (pin "2") (pinfunction "2_2") (pintype "passive"))
      (node (ref "C31") (pin "2") (pinfunction "2_2") (pintype "passive"))
      (node (ref "C32") (pin "2") (pinfunction "2_2") (pintype "passive"))
      (node (ref "C33") (pin "1") (pinfunction "1_1") (pintype "passive"))
      (node (ref "C34") (pin "1") (pinfunction "1_1") (pintype "passive"))
      (node (ref "C35") (pin "1") (pinfunction "1_1") (pintype "passive"))
      (node (ref "C4") (pin "2") (pinfunction "2_2") (pintype "passive"))
      (node (ref "C43") (pin "1") (pinfunction "1_1") (pintype "passive"))
      (node (ref "C5") (pin "2") (pinfunction "2_2") (pintype "passive"))
      (node (ref "C6") (pin "2") (pinfunction "2_2") (pintype "passive"))
      (node (ref "C7") (pin "2") (pinfunction "2_2") (pintype "passive"))
      (node (ref "C8") (pin "2") (pinfunction "2_2") (pintype "passive"))
      (node (ref "C9") (pin "2") (pinfunction "2_2") (pintype "passive"))
      (node (ref "D1") (pin "1") (pinfunction "1_1") (pintype "passive"))
      (node (ref "D2") (pin "2") (pinfunction "C_2") (pintype "passive"))
      (node (ref "P10") (pin "3") (pinfunction "3_3") (pintype "passive"))
      (node (ref "P11") (pin "3") (pinfunction "3_3") (pintype "passive"))
      (node (ref "P13") (pin "2") (pinfunction "2_2") (pintype "passive"))
      (node (ref "P16") (pin "4") (pinfunction "4_4") (pintype "passive"))
      (node (ref "P17") (pin "3") (pinfunction "3_3") (pintype "passive"))
      (node (ref "P17") (pin "4") (pinfunction "4_4") (pintype "passive"))
      (node (ref "P5") (pin "3") (pinfunction "3_3") (pintype "passive"))
      (node (ref "P5") (pin "4") (pinfunction "4_4") (pintype "passive"))
      (node (ref "P7") (pin "3") (pinfunction "3_3") (pintype "passive"))
      (node (ref "P7") (pin "4") (pinfunction "4_4") (pintype "passive"))
      (node (ref "P8") (pin "3") (pinfunction "3_3") (pintype "passive"))
      (node (ref "P9") (pin "3") (pinfunction "3_3") (pintype "passive"))
      (node (ref "Q4") (pin "2") (pinfunction "E_2") (pintype "passive"))
      (node (ref "U16") (pin "2") (pinfunction "VSS_2") (pintype "passive"))
      (node (ref "U18") (pin "2") (pinfunction "GND_2") (pintype "passive"))
    )
    (net (code "47") (name "Net-(C32-Pad1)") (class "Default")
      (node (ref "C32") (pin "1") (pinfunction "1_1") (pintype "passive"))
      (node (ref "R2") (pin "1") (pinfunction "1_1") (pintype "passive"))
      (node (ref "R3") (pin "2") (pinfunction "2_2") (pintype "passive"))
    )
    (net (code "48") (name "Net-(P1-Pad1)") (class "Default")
      (node (ref "P1") (pin "1") (pinfunction "1_1") (pintype "passive"))
      (node (ref "U1") (pin "1") (pinfunction "1_1") (pintype "passive"))
      (node (ref "U5") (pin "1") (pinfunction "1_1") (pintype "passive"))
    )
    (net (code "49") (name "Net-(P1-Pad2)") (class "Default")
      (node (ref "P1") (pin "2") (pinfunction "2_2") (pintype "passive"))
      (node (ref "U1") (pin "2") (pinfunction "2_2") (pintype "passive"))
      (node (ref "U5") (pin "2") (pinfunction "2_2") (pintype "passive"))
    )
    (net (code "50") (name "Net-(P1-Pad3)") (class "Default")
      (node (ref "P1") (pin "3") (pinfunction "3_3") (pintype "passive"))
      (node (ref "U1") (pin "3") (pinfunction "3_3") (pintype "passive"))
      (node (ref "U5") (pin "3") (pinfunction "3_3") (pintype "passive"))
    )
    (net (code "51") (name "Net-(P1-Pad4)") (class "Default")
      (node (ref "P1") (pin "4") (pinfunction "4_4") (pintype "passive"))
      (node (ref "U1") (pin "4") (pinfunction "4_4") (pintype "passive"))
      (node (ref "U5") (pin "4") (pinfunction "4_4") (pintype "passive"))
    )
    (net (code "52") (name "Net-(P1-Pad5)") (class "Default")
      (node (ref "P1") (pin "5") (pinfunction "5_5") (pintype "passive"))
      (node (ref "U2") (pin "1") (pinfunction "1_1") (pintype "passive"))
      (node (ref "U7") (pin "1") (pinfunction "1_1") (pintype "passive"))
    )
    (net (code "53") (name "Net-(P1-Pad6)") (class "Default")
      (node (ref "P1") (pin "6") (pinfunction "6_6") (pintype "passive"))
      (node (ref "U2") (pin "2") (pinfunction "2_2") (pintype "passive"))
      (node (ref "U7") (pin "2") (pinfunction "2_2") (pintype "passive"))
    )
    (net (code "54") (name "Net-(P1-Pad7)") (class "Default")
      (node (ref "P1") (pin "7") (pinfunction "7_7") (pintype "passive"))
      (node (ref "U2") (pin "3") (pinfunction "3_3") (pintype "passive"))
      (node (ref "U7") (pin "3") (pinfunction "3_3") (pintype "passive"))
    )
    (net (code "55") (name "Net-(P1-Pad8)") (class "Default")
      (node (ref "P1") (pin "8") (pinfunction "8_8") (pintype "passive"))
      (node (ref "U2") (pin "4") (pinfunction "4_4") (pintype "passive"))
      (node (ref "U7") (pin "4") (pinfunction "4_4") (pintype "passive"))
    )
    (net (code "56") (name "Net-(P2-Pad1)") (class "Default")
      (node (ref "P2") (pin "1") (pinfunction "1_1") (pintype "passive"))
      (node (ref "U4") (pin "1") (pinfunction "1_1") (pintype "passive"))
      (node (ref "U6") (pin "1") (pinfunction "1_1") (pintype "passive"))
    )
    (net (code "57") (name "Net-(P2-Pad2)") (class "Default")
      (node (ref "P2") (pin "2") (pinfunction "2_2") (pintype "passive"))
      (node (ref "U4") (pin "2") (pinfunction "2_2") (pintype "passive"))
      (node (ref "U6") (pin "2") (pinfunction "2_2") (pintype "passive"))
    )
    (net (code "58") (name "Net-(P2-Pad3)") (class "Default")
      (node (ref "P2") (pin "3") (pinfunction "3_3") (pintype "passive"))
      (node (ref "U4") (pin "3") (pinfunction "3_3") (pintype "passive"))
      (node (ref "U6") (pin "3") (pinfunction "3_3") (pintype "passive"))
    )
    (net (code "59") (name "Net-(P2-Pad4)") (class "Default")
      (node (ref "P2") (pin "4") (pinfunction "4_4") (pintype "passive"))
      (node (ref "U4") (pin "4") (pinfunction "4_4") (pintype "passive"))
      (node (ref "U6") (pin "4") (pinfunction "4_4") (pintype "passive"))
    )
    (net (code "60") (name "Net-(P2-Pad6)") (class "Default")
      (node (ref "P2") (pin "6") (pinfunction "6_6") (pintype "passive"))
      (node (ref "U3") (pin "2") (pinfunction "2_2") (pintype "passive"))
      (node (ref "U8") (pin "2") (pinfunction "2_2") (pintype "passive"))
    )
    (net (code "61") (name "Net-(P2-Pad7)") (class "Default")
      (node (ref "P2") (pin "7") (pinfunction "7_7") (pintype "passive"))
      (node (ref "U3") (pin "3") (pinfunction "3_3") (pintype "passive"))
      (node (ref "U8") (pin "3") (pinfunction "3_3") (pintype "passive"))
    )
    (net (code "62") (name "Net-(P2-Pad8)") (class "Default")
      (node (ref "P2") (pin "8") (pinfunction "8_8") (pintype "passive"))
      (node (ref "U3") (pin "4") (pinfunction "4_4") (pintype "passive"))
      (node (ref "U8") (pin "4") (pinfunction "4_4") (pintype "passive"))
    )
    (net (code "63") (name "Net-(P3-Pad1)") (class "Default")
      (node (ref "P3") (pin "1") (pinfunction "1_1") (pintype "passive"))
      (node (ref "U13") (pin "1") (pinfunction "1_1") (pintype "passive"))
      (node (ref "U14") (pin "1") (pinfunction "1_1") (pintype "passive"))
    )
    (net (code "64") (name "Net-(P3-Pad2)") (class "Default")
      (node (ref "P3") (pin "2") (pinfunction "2_2") (pintype "passive"))
      (node (ref "U13") (pin "2") (pinfunction "2_2") (pintype "passive"))
      (node (ref "U14") (pin "2") (pinfunction "2_2") (pintype "passive"))
    )
    (net (code "65") (name "Net-(P3-Pad3)") (class "Default")
      (node (ref "P3") (pin "3") (pinfunction "3_3") (pintype "passive"))
      (node (ref "U13") (pin "3") (pinfunction "3_3") (pintype "passive"))
      (node (ref "U14") (pin "3") (pinfunction "3_3") (pintype "passive"))
    )
    (net (code "66") (name "Net-(P3-Pad4)") (class "Default")
      (node (ref "P3") (pin "4") (pinfunction "4_4") (pintype "passive"))
      (node (ref "U13") (pin "4") (pinfunction "4_4") (pintype "passive"))
      (node (ref "U14") (pin "4") (pinfunction "4_4") (pintype "passive"))
    )
    (net (code "67") (name "Net-(P4-Pad1)") (class "Default")
      (node (ref "P4") (pin "1") (pinfunction "1_1") (pintype "passive"))
      (node (ref "U11") (pin "1") (pinfunction "1_1") (pintype "passive"))
      (node (ref "U9") (pin "1") (pinfunction "1_1") (pintype "passive"))
    )
    (net (code "68") (name "Net-(P4-Pad2)") (class "Default")
      (node (ref "P4") (pin "2") (pinfunction "2_2") (pintype "passive"))
      (node (ref "U11") (pin "2") (pinfunction "2_2") (pintype "passive"))
      (node (ref "U9") (pin "2") (pinfunction "2_2") (pintype "passive"))
    )
    (net (code "69") (name "Net-(P4-Pad3)") (class "Default")
      (node (ref "P4") (pin "3") (pinfunction "3_3") (pintype "passive"))
      (node (ref "U11") (pin "3") (pinfunction "3_3") (pintype "passive"))
      (node (ref "U9") (pin "3") (pinfunction "3_3") (pintype "passive"))
    )
    (net (code "70") (name "Net-(P4-Pad4)") (class "Default")
      (node (ref "P4") (pin "4") (pinfunction "4_4") (pintype "passive"))
      (node (ref "U11") (pin "4") (pinfunction "4_4") (pintype "passive"))
      (node (ref "U9") (pin "4") (pinfunction "4_4") (pintype "passive"))
    )
    (net (code "71") (name "Net-(P4-Pad5)") (class "Default")
      (node (ref "P4") (pin "5") (pinfunction "5_5") (pintype "passive"))
      (node (ref "U10") (pin "1") (pinfunction "1_1") (pintype "passive"))
      (node (ref "U12") (pin "1") (pinfunction "1_1") (pintype "passive"))
    )
    (net (code "72") (name "Net-(P4-Pad6)") (class "Default")
      (node (ref "P4") (pin "6") (pinfunction "6_6") (pintype "passive"))
      (node (ref "U10") (pin "2") (pinfunction "2_2") (pintype "passive"))
      (node (ref "U12") (pin "2") (pinfunction "2_2") (pintype "passive"))
    )
    (net (code "73") (name "Net-(P4-Pad7)") (class "Default")
      (node (ref "P4") (pin "7") (pinfunction "7_7") (pintype "passive"))
      (node (ref "U10") (pin "3") (pinfunction "3_3") (pintype "passive"))
      (node (ref "U12") (pin "3") (pinfunction "3_3") (pintype "passive"))
    )
    (net (code "74") (name "Net-(P4-Pad8)") (class "Default")
      (node (ref "P4") (pin "8") (pinfunction "8_8") (pintype "passive"))
      (node (ref "U10") (pin "4") (pinfunction "4_4") (pintype "passive"))
      (node (ref "U12") (pin "4") (pinfunction "4_4") (pintype "passive"))
    )
    (net (code "75") (name "Net-(Q3-G)") (class "Default")
      (node (ref "Q3") (pin "1") (pinfunction "G_1") (pintype "passive"))
      (node (ref "Q4") (pin "3") (pinfunction "C_3") (pintype "passive"))
      (node (ref "R10") (pin "1") (pinfunction "1_1") (pintype "passive"))
    )
    (net (code "76") (name "Net-(U18-EN)") (class "Default")
      (node (ref "R9") (pin "2") (pinfunction "2_2") (pintype "passive"))
      (node (ref "U18") (pin "3") (pinfunction "EN_3") (pintype "passive"))
    )
    (net (code "77") (name "unconnected-(D1-K-Pad3)") (class "Default")
      (node (ref "D1") (pin "3") (pinfunction "K_3") (pintype "passive"))
    )
    (net (code "78") (name "unconnected-(D2-K-Pad3)") (class "Default")
      (node (ref "D2") (pin "3") (pinfunction "K_3") (pintype "passive"))
    )
    (net (code "79") (name "unconnected-(P2-Pad5)") (class "Default")
      (node (ref "P2") (pin "5") (pinfunction "5_5") (pintype "passive"))
    )
    (net (code "80") (name "unconnected-(U3-Pad1)") (class "Default")
      (node (ref "U3") (pin "1") (pinfunction "1_1") (pintype "passive"))
    )
    (net (code "81") (name "unconnected-(U8-Pad1)") (class "Default")
      (node (ref "U8") (pin "1") (pinfunction "1_1") (pintype "passive"))
    )
    (net (code "82") (name "unconnected-(U8-Pad8)") (class "Default")
      (node (ref "U8") (pin "8") (pinfunction "8_8") (pintype "passive"))
    )
    (net (code "83") (name "unconnected-(U18-NC-Pad4)") (class "Default")
      (node (ref "U18") (pin "4") (pinfunction "NC_4") (pintype "passive"))
    )
  )
)
